# AUAV-X1_FMU_R1.net
KiCad netlist of a schematic drawn in Altium Designer
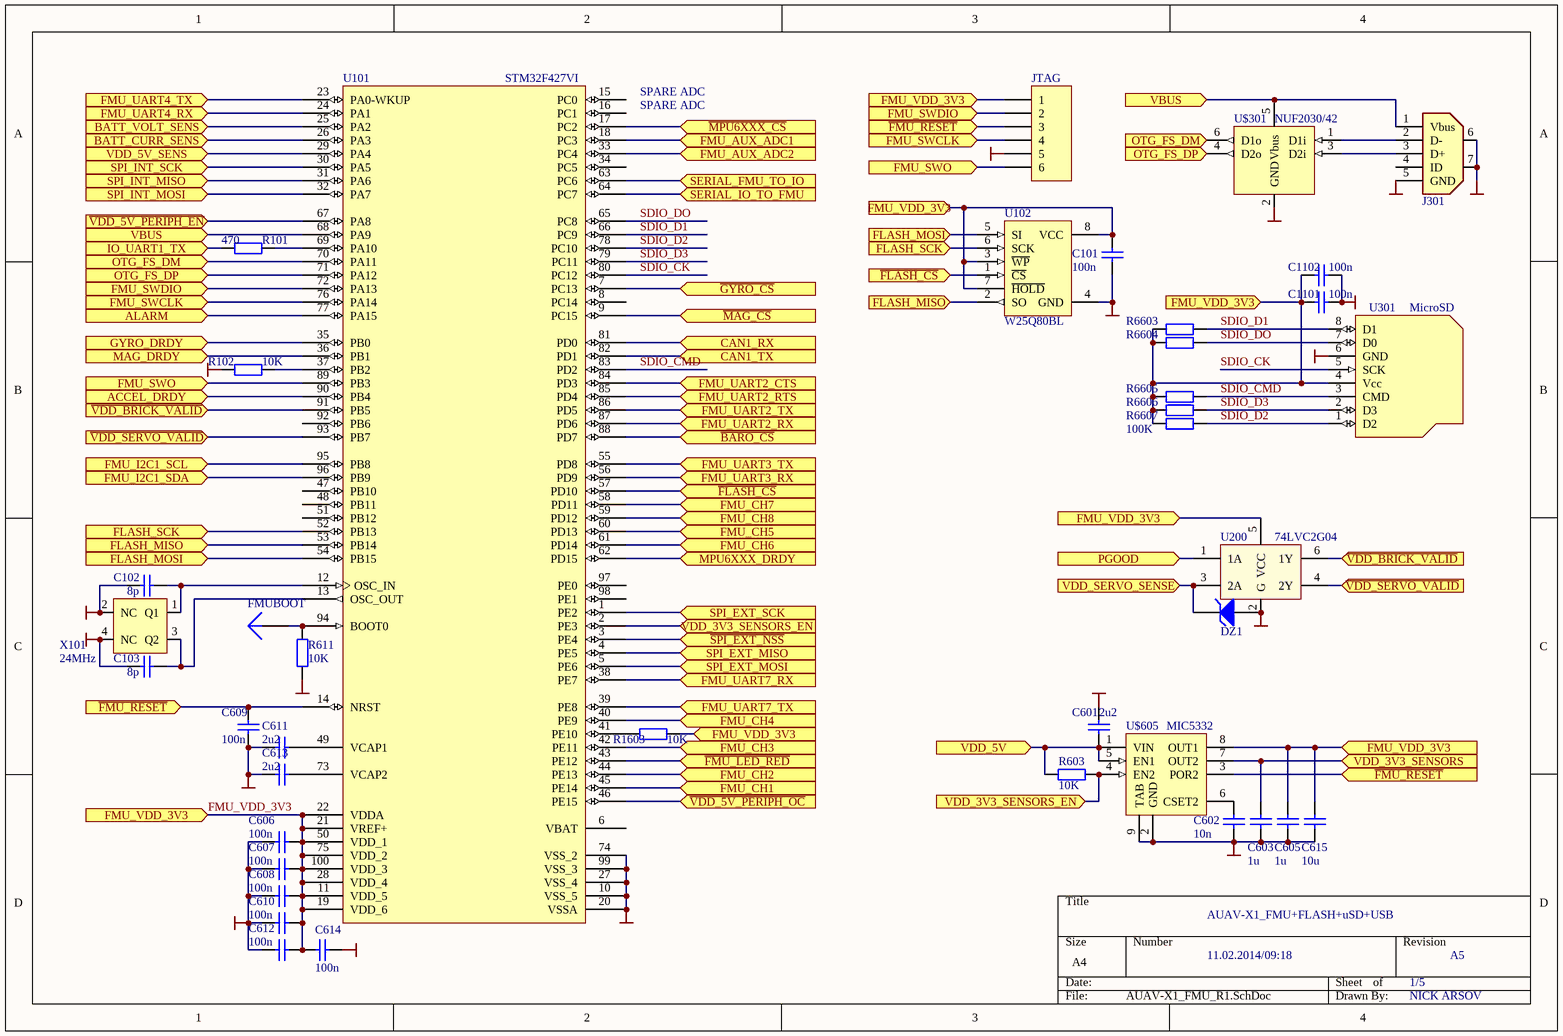
[diagram p0: AUAV-X1_FMU_R1.SchDoc]

(export (version "E")
  (design (tool "Eeschema 10.0.6"))
  (components
    (comp (ref "C101")
      (value "100n")
      (footprint "0402A")
      (description "Capacitor")
      (fields (field (name "PUBLISHER") "Altium Limited"))
      (libsource (lib "Miscellaneous Devices") (part "Cap"))
    )
    (comp (ref "C102")
      (value "8p")
      (footprint "0402A")
      (description "Capacitor")
      (fields (field (name "PUBLISHER") "Altium Limited"))
      (libsource (lib "Miscellaneous Devices") (part "Cap"))
    )
    (comp (ref "C103")
      (value "8p")
      (footprint "0402A")
      (description "Capacitor")
      (fields (field (name "PUBLISHER") "Altium Limited"))
      (libsource (lib "Miscellaneous Devices") (part "Cap"))
    )
    (comp (ref "C601")
      (value "2u2")
      (footprint "0402A")
      (description "Capacitor")
      (fields (field (name "PUBLISHER") "Altium Limited"))
      (libsource (lib "Miscellaneous Devices") (part "Cap"))
    )
    (comp (ref "C602")
      (value "10n")
      (footprint "0402A")
      (description "Capacitor")
      (fields (field (name "PUBLISHER") "Altium Limited"))
      (libsource (lib "Miscellaneous Devices") (part "Cap"))
    )
    (comp (ref "C603")
      (value "1u")
      (footprint "0402A")
      (description "Capacitor")
      (fields (field (name "PUBLISHER") "Altium Limited"))
      (libsource (lib "Miscellaneous Devices") (part "Cap"))
    )
    (comp (ref "C605")
      (value "1u")
      (footprint "0402A")
      (description "Capacitor")
      (fields (field (name "PUBLISHER") "Altium Limited"))
      (libsource (lib "Miscellaneous Devices") (part "Cap"))
    )
    (comp (ref "C606")
      (value "100n")
      (footprint "0402A")
      (description "Capacitor")
      (fields (field (name "PUBLISHER") "Altium Limited"))
      (libsource (lib "Miscellaneous Devices") (part "Cap"))
    )
    (comp (ref "C607")
      (value "100n")
      (footprint "0402A")
      (description "Capacitor")
      (fields (field (name "PUBLISHER") "Altium Limited"))
      (libsource (lib "Miscellaneous Devices") (part "Cap"))
    )
    (comp (ref "C608")
      (value "100n")
      (footprint "0402A")
      (description "Capacitor")
      (fields (field (name "PUBLISHER") "Altium Limited"))
      (libsource (lib "Miscellaneous Devices") (part "Cap"))
    )
    (comp (ref "C609")
      (value "100n")
      (footprint "0402A")
      (description "Capacitor")
      (fields (field (name "PUBLISHER") "Altium Limited"))
      (libsource (lib "Miscellaneous Devices") (part "Cap"))
    )
    (comp (ref "C610")
      (value "100n")
      (footprint "0402A")
      (description "Capacitor")
      (fields (field (name "PUBLISHER") "Altium Limited"))
      (libsource (lib "Miscellaneous Devices") (part "Cap"))
    )
    (comp (ref "C611")
      (value "2u2")
      (footprint "0402A")
      (description "Capacitor")
      (fields (field (name "PUBLISHER") "Altium Limited"))
      (libsource (lib "Miscellaneous Devices") (part "Cap"))
    )
    (comp (ref "C612")
      (value "100n")
      (footprint "0402A")
      (description "Capacitor")
      (fields (field (name "PUBLISHER") "Altium Limited"))
      (libsource (lib "Miscellaneous Devices") (part "Cap"))
    )
    (comp (ref "C613")
      (value "2u2")
      (footprint "0402A")
      (description "Capacitor")
      (fields (field (name "PUBLISHER") "Altium Limited"))
      (libsource (lib "Miscellaneous Devices") (part "Cap"))
    )
    (comp (ref "C614")
      (value "100n")
      (footprint "0402A")
      (description "Capacitor")
      (fields (field (name "PUBLISHER") "Altium Limited"))
      (libsource (lib "Miscellaneous Devices") (part "Cap"))
    )
    (comp (ref "C615")
      (value "10u")
      (footprint "0402A")
      (description "Capacitor")
      (fields (field (name "PUBLISHER") "Altium Limited"))
      (libsource (lib "Miscellaneous Devices") (part "Cap"))
    )
    (comp (ref "C1101")
      (value "100n")
      (footprint "0402A")
      (description "Capacitor")
      (fields (field (name "PUBLISHER") "Altium Limited"))
      (libsource (lib "Miscellaneous Devices") (part "Cap"))
    )
    (comp (ref "C1102")
      (value "100n")
      (footprint "0402A")
      (description "Capacitor")
      (fields (field (name "PUBLISHER") "Altium Limited"))
      (libsource (lib "Miscellaneous Devices") (part "Cap"))
    )
    (comp (ref "DZ1")
      (value "D Zener")
      (footprint "SOD-523")
      (description "Zener Diode")
      (fields (field (name "PUBLISHER") "Altium Limited"))
      (libsource (lib "Miscellaneous Devices") (part "D Zener"))
    )
    (comp (ref "FMUBOOT")
      (value "Plug")
      (footprint "PAD1")
      (fields (field (name "PUBLISHER") "Altium Limited"))
      (libsource (lib "Miscellaneous Connectors") (part "Plug"))
    )
    (comp (ref "J301")
      (value "miniUSB")
      (footprint "USBmicro_B")
      (libsource (lib "My_Altium") (part "MicroUSB"))
    )
    (comp (ref "JTAG")
      (value "Header 6")
      (footprint "JTAG_TC2030")
      (description "Header, 6-Pin")
      (fields (field (name "PUBLISHER") "Altium Limited"))
      (libsource (lib "Miscellaneous Connectors") (part "Header 6"))
    )
    (comp (ref "R101")
      (value "470")
      (footprint "0402A")
      (description "Resistor")
      (fields (field (name "PUBLISHER") "Altium Limited"))
      (libsource (lib "") (part "Res2_1"))
    )
    (comp (ref "R102")
      (value "10K")
      (footprint "0402A")
      (description "Resistor")
      (fields (field (name "PUBLISHER") "Altium Limited"))
      (libsource (lib "") (part "Res2_1"))
    )
    (comp (ref "R603")
      (value "10K")
      (footprint "0402A")
      (description "Resistor")
      (fields (field (name "PUBLISHER") "Altium Limited"))
      (libsource (lib "") (part "Res2_1"))
    )
    (comp (ref "R611")
      (value "10K")
      (footprint "0402A")
      (description "Resistor")
      (fields (field (name "PUBLISHER") "Altium Limited"))
      (libsource (lib "Miscellaneous Devices") (part "Res2"))
    )
    (comp (ref "R1603")
      (value "10K")
      (footprint "0402A")
      (description "Resistor")
      (fields (field (name "PUBLISHER") "Altium Limited"))
      (libsource (lib "") (part "Res2_1"))
    )
    (comp (ref "R6603")
      (value "100K")
      (footprint "0402A")
      (description "Resistor")
      (fields (field (name "PUBLISHER") "Altium Limited"))
      (libsource (lib "") (part "Res2_1"))
    )
    (comp (ref "R6604")
      (value "100K")
      (footprint "0402A")
      (description "Resistor")
      (fields (field (name "PUBLISHER") "Altium Limited"))
      (libsource (lib "") (part "Res2_1"))
    )
    (comp (ref "R6605")
      (value "100K")
      (footprint "0402A")
      (description "Resistor")
      (fields (field (name "PUBLISHER") "Altium Limited"))
      (libsource (lib "") (part "Res2_1"))
    )
    (comp (ref "R6606")
      (value "100K")
      (footprint "0402A")
      (description "Resistor")
      (fields (field (name "PUBLISHER") "Altium Limited"))
      (libsource (lib "") (part "Res2_1"))
    )
    (comp (ref "R6607")
      (value "100K")
      (footprint "0402A")
      (description "Resistor")
      (fields (field (name "PUBLISHER") "Altium Limited"))
      (libsource (lib "") (part "Res2_1"))
    )
    (comp (ref "U$301")
      (value "NUF2030/42")
      (footprint "NUF2030_SOT563")
      (libsource (lib "My_Altium") (part "NUF2030/42"))
    )
    (comp (ref "U$605")
      (value "MIC5332")
      (footprint "MIC5332")
      (libsource (lib "My_Altium") (part "MIC5332"))
    )
    (comp (ref "U101")
      (value "STM32F427VI")
      (footprint "LQFP100_L")
      (description "STM32 ARM-based 32-bit MCU with 64 Kbytes Flash, 100-pin LQFP, Industrial Temperature")
      (fields (field (name "PUBLISHER") "Altium Limited"))
      (libsource (lib "ST Microcontroller 32-Bit STM32") (part "STM32F103VBT6"))
    )
    (comp (ref "U102")
      (value "W25Q80BL")
      (footprint "W25Q80BL_WSON5X6")
      (libsource (lib "My_Altium") (part "AT45DB161D-MU"))
    )
    (comp (ref "U200")
      (value "74LVC2G04")
      (footprint "SOT363_L")
      (libsource (lib "My_Altium") (part "74LVC2G04"))
    )
    (comp (ref "U301")
      (value "MicroSD")
      (footprint "MicroSD_China_01")
      (libsource (lib "My_Altium") (part "MicroSD"))
    )
    (comp (ref "X101")
      (value "24MHz")
      (footprint "Crystal_2.5x2")
      (libsource (lib "My_Altium") (part "Crystal_4pin"))
    )
  )
  (nets
    (net (code "1") (name "/ACCEL_DRDY") (class "Default")
      (node (ref "U101") (pin "90") (pinfunction "PB4_90") (pintype "bidirectional"))
    )
    (net (code "2") (name "/ALARM") (class "Default")
      (node (ref "U101") (pin "77") (pinfunction "PA15_77") (pintype "bidirectional"))
    )
    (net (code "3") (name "/BATT_CURR_SENS") (class "Default")
      (node (ref "U101") (pin "26") (pinfunction "PA3_26") (pintype "bidirectional"))
    )
    (net (code "4") (name "/BATT_VOLT_SENS") (class "Default")
      (node (ref "U101") (pin "25") (pinfunction "PA2_25") (pintype "bidirectional"))
    )
    (net (code "5") (name "/CAN1_RX") (class "Default")
      (node (ref "U101") (pin "81") (pinfunction "PD0_81") (pintype "bidirectional"))
    )
    (net (code "6") (name "/CAN1_TX") (class "Default")
      (node (ref "U101") (pin "82") (pinfunction "PD1_82") (pintype "bidirectional"))
    )
    (net (code "7") (name "/FLASH_MISO") (class "Default")
      (node (ref "U101") (pin "53") (pinfunction "PB14_53") (pintype "bidirectional"))
      (node (ref "U102") (pin "2") (pinfunction "SO_2") (pintype "output"))
    )
    (net (code "8") (name "/FLASH_MOSI") (class "Default")
      (node (ref "U101") (pin "54") (pinfunction "PB15_54") (pintype "bidirectional"))
      (node (ref "U102") (pin "5") (pinfunction "SI_5") (pintype "input"))
    )
    (net (code "9") (name "/FLASH_SCK") (class "Default")
      (node (ref "U101") (pin "52") (pinfunction "PB13_52") (pintype "bidirectional"))
      (node (ref "U102") (pin "6") (pinfunction "SCK_6") (pintype "input"))
    )
    (net (code "10") (name "/FMU_AUX_ADC1") (class "Default")
      (node (ref "U101") (pin "18") (pinfunction "PC3_18") (pintype "bidirectional"))
    )
    (net (code "11") (name "/FMU_AUX_ADC2") (class "Default")
      (node (ref "U101") (pin "33") (pinfunction "PC4_33") (pintype "bidirectional"))
    )
    (net (code "12") (name "/FMU_CH1") (class "Default")
      (node (ref "U101") (pin "45") (pinfunction "PE14_45") (pintype "bidirectional"))
    )
    (net (code "13") (name "/FMU_CH2") (class "Default")
      (node (ref "U101") (pin "44") (pinfunction "PE13_44") (pintype "bidirectional"))
    )
    (net (code "14") (name "/FMU_CH3") (class "Default")
      (node (ref "U101") (pin "42") (pinfunction "PE11_42") (pintype "bidirectional"))
    )
    (net (code "15") (name "/FMU_CH4") (class "Default")
      (node (ref "U101") (pin "40") (pinfunction "PE9_40") (pintype "bidirectional"))
    )
    (net (code "16") (name "/FMU_CH5") (class "Default")
      (node (ref "U101") (pin "60") (pinfunction "PD13_60") (pintype "bidirectional"))
    )
    (net (code "17") (name "/FMU_CH6") (class "Default")
      (node (ref "U101") (pin "61") (pinfunction "PD14_61") (pintype "bidirectional"))
    )
    (net (code "18") (name "/FMU_CH7") (class "Default")
      (node (ref "U101") (pin "58") (pinfunction "PD11_58") (pintype "bidirectional"))
    )
    (net (code "19") (name "/FMU_CH8") (class "Default")
      (node (ref "U101") (pin "59") (pinfunction "PD12_59") (pintype "bidirectional"))
    )
    (net (code "20") (name "/FMU_I2C1_SCL") (class "Default")
      (node (ref "U101") (pin "95") (pinfunction "PB8_95") (pintype "bidirectional"))
    )
    (net (code "21") (name "/FMU_I2C1_SDA") (class "Default")
      (node (ref "U101") (pin "96") (pinfunction "PB9_96") (pintype "bidirectional"))
    )
    (net (code "22") (name "/FMU_SWCLK") (class "Default")
      (node (ref "JTAG") (pin "4") (pinfunction "4_4") (pintype "passive"))
      (node (ref "U101") (pin "76") (pinfunction "PA14_76") (pintype "bidirectional"))
    )
    (net (code "23") (name "/FMU_SWDIO") (class "Default")
      (node (ref "JTAG") (pin "2") (pinfunction "2_2") (pintype "passive"))
      (node (ref "U101") (pin "72") (pinfunction "PA13_72") (pintype "bidirectional"))
    )
    (net (code "24") (name "/FMU_SWO") (class "Default")
      (node (ref "JTAG") (pin "6") (pinfunction "6_6") (pintype "passive"))
      (node (ref "U101") (pin "89") (pinfunction "PB3_89") (pintype "bidirectional"))
    )
    (net (code "25") (name "/FMU_UART2_CTS") (class "Default")
      (node (ref "U101") (pin "84") (pinfunction "PD3_84") (pintype "bidirectional"))
    )
    (net (code "26") (name "/FMU_UART2_RTS") (class "Default")
      (node (ref "U101") (pin "85") (pinfunction "PD4_85") (pintype "bidirectional"))
    )
    (net (code "27") (name "/FMU_UART2_RX") (class "Default")
      (node (ref "U101") (pin "87") (pinfunction "PD6_87") (pintype "bidirectional"))
    )
    (net (code "28") (name "/FMU_UART2_TX") (class "Default")
      (node (ref "U101") (pin "86") (pinfunction "PD5_86") (pintype "bidirectional"))
    )
    (net (code "29") (name "/FMU_UART3_RX") (class "Default")
      (node (ref "U101") (pin "56") (pinfunction "PD9_56") (pintype "bidirectional"))
    )
    (net (code "30") (name "/FMU_UART3_TX") (class "Default")
      (node (ref "U101") (pin "55") (pinfunction "PD8_55") (pintype "bidirectional"))
    )
    (net (code "31") (name "/FMU_UART4_RX") (class "Default")
      (node (ref "U101") (pin "24") (pinfunction "PA1_24") (pintype "bidirectional"))
    )
    (net (code "32") (name "/FMU_UART4_TX") (class "Default")
      (node (ref "U101") (pin "23") (pinfunction "PA0-WKUP_23") (pintype "bidirectional"))
    )
    (net (code "33") (name "/FMU_UART7_RX") (class "Default")
      (node (ref "U101") (pin "38") (pinfunction "PE7_38") (pintype "bidirectional"))
    )
    (net (code "34") (name "/FMU_UART7_TX") (class "Default")
      (node (ref "U101") (pin "39") (pinfunction "PE8_39") (pintype "bidirectional"))
    )
    (net (code "35") (name "/FMU_VDD_3V3") (class "Default")
      (node (ref "C101") (pin "2") (pinfunction "2_2") (pintype "passive"))
      (node (ref "C1101") (pin "2") (pinfunction "2_2") (pintype "passive"))
      (node (ref "C1102") (pin "2") (pinfunction "2_2") (pintype "passive"))
      (node (ref "C605") (pin "2") (pinfunction "2_2") (pintype "passive"))
      (node (ref "C606") (pin "2") (pinfunction "2_2") (pintype "passive"))
      (node (ref "C607") (pin "2") (pinfunction "2_2") (pintype "passive"))
      (node (ref "C608") (pin "2") (pinfunction "2_2") (pintype "passive"))
      (node (ref "C610") (pin "2") (pinfunction "2_2") (pintype "passive"))
      (node (ref "C612") (pin "2") (pinfunction "2_2") (pintype "passive"))
      (node (ref "C614") (pin "2") (pinfunction "2_2") (pintype "passive"))
      (node (ref "C615") (pin "2") (pinfunction "2_2") (pintype "passive"))
      (node (ref "JTAG") (pin "1") (pinfunction "1_1") (pintype "passive"))
      (node (ref "R1603") (pin "2") (pinfunction "2_2") (pintype "passive"))
      (node (ref "R6603") (pin "1") (pinfunction "1_1") (pintype "passive"))
      (node (ref "R6604") (pin "1") (pinfunction "1_1") (pintype "passive"))
      (node (ref "R6605") (pin "1") (pinfunction "1_1") (pintype "passive"))
      (node (ref "R6606") (pin "1") (pinfunction "1_1") (pintype "passive"))
      (node (ref "R6607") (pin "1") (pinfunction "1_1") (pintype "passive"))
      (node (ref "U$605") (pin "8") (pinfunction "OUT1_8") (pintype "passive"))
      (node (ref "U101") (pin "100") (pinfunction "VDD_3_100") (pintype "power_in"))
      (node (ref "U101") (pin "11") (pinfunction "VDD_5_11") (pintype "power_in"))
      (node (ref "U101") (pin "19") (pinfunction "VDD_6_19") (pintype "power_in"))
      (node (ref "U101") (pin "21") (pinfunction "VREF+_21") (pintype "power_in"))
      (node (ref "U101") (pin "22") (pinfunction "VDDA_22") (pintype "power_in"))
      (node (ref "U101") (pin "28") (pinfunction "VDD_4_28") (pintype "power_in"))
      (node (ref "U101") (pin "50") (pinfunction "VDD_1_50") (pintype "power_in"))
      (node (ref "U101") (pin "75") (pinfunction "VDD_2_75") (pintype "power_in"))
      (node (ref "U102") (pin "3") (pinfunction "~{WP}_3") (pintype "input"))
      (node (ref "U102") (pin "7") (pinfunction "~{HOLD}_7") (pintype "passive"))
      (node (ref "U102") (pin "8") (pinfunction "VCC_8") (pintype "power_in"))
      (node (ref "U200") (pin "5") (pinfunction "VCC_5") (pintype "power_in"))
      (node (ref "U301") (pin "4") (pinfunction "Vcc_4") (pintype "power_in"))
    )
    (net (code "36") (name "/GYRO_DRDY") (class "Default")
      (node (ref "U101") (pin "35") (pinfunction "PB0_35") (pintype "bidirectional"))
    )
    (net (code "37") (name "/IO_UART1_TX") (class "Default")
      (node (ref "R101") (pin "1") (pinfunction "1_1") (pintype "passive"))
    )
    (net (code "38") (name "/MAG_DRDY") (class "Default")
      (node (ref "U101") (pin "36") (pinfunction "PB1_36") (pintype "bidirectional"))
    )
    (net (code "39") (name "/MPU6XXX_DRDY") (class "Default")
      (node (ref "U101") (pin "62") (pinfunction "PD15_62") (pintype "bidirectional"))
    )
    (net (code "40") (name "/OTG_FS_DM") (class "Default")
      (node (ref "U$301") (pin "6") (pinfunction "D1o_6") (pintype "output"))
      (node (ref "U101") (pin "70") (pinfunction "PA11_70") (pintype "bidirectional"))
    )
    (net (code "41") (name "/OTG_FS_DP") (class "Default")
      (node (ref "U$301") (pin "4") (pinfunction "D2o_4") (pintype "output"))
      (node (ref "U101") (pin "71") (pinfunction "PA12_71") (pintype "bidirectional"))
    )
    (net (code "42") (name "/PGOOD") (class "Default")
      (node (ref "U200") (pin "1") (pinfunction "1A_1") (pintype "passive"))
    )
    (net (code "43") (name "/SDIO_CK") (class "Default")
      (node (ref "U101") (pin "80") (pinfunction "PC12_80") (pintype "bidirectional"))
      (node (ref "U301") (pin "5") (pinfunction "SCK_5") (pintype "input"))
    )
    (net (code "44") (name "/SDIO_CMD") (class "Default")
      (node (ref "R6605") (pin "2") (pinfunction "2_2") (pintype "passive"))
      (node (ref "U101") (pin "83") (pinfunction "PD2_83") (pintype "bidirectional"))
      (node (ref "U301") (pin "3") (pinfunction "CMD_3") (pintype "passive"))
    )
    (net (code "45") (name "/SDIO_D1") (class "Default")
      (node (ref "R6603") (pin "2") (pinfunction "2_2") (pintype "passive"))
      (node (ref "U101") (pin "66") (pinfunction "PC9_66") (pintype "bidirectional"))
      (node (ref "U301") (pin "8") (pinfunction "D1_8") (pintype "bidirectional"))
    )
    (net (code "46") (name "/SDIO_D2") (class "Default")
      (node (ref "R6607") (pin "2") (pinfunction "2_2") (pintype "passive"))
      (node (ref "U101") (pin "78") (pinfunction "PC10_78") (pintype "bidirectional"))
      (node (ref "U301") (pin "1") (pinfunction "D2_1") (pintype "bidirectional"))
    )
    (net (code "47") (name "/SDIO_D3") (class "Default")
      (node (ref "R6606") (pin "2") (pinfunction "2_2") (pintype "passive"))
      (node (ref "U101") (pin "79") (pinfunction "PC11_79") (pintype "bidirectional"))
      (node (ref "U301") (pin "2") (pinfunction "D3_2") (pintype "bidirectional"))
    )
    (net (code "48") (name "/SDIO_DO") (class "Default")
      (node (ref "R6604") (pin "2") (pinfunction "2_2") (pintype "passive"))
      (node (ref "U101") (pin "65") (pinfunction "PC8_65") (pintype "bidirectional"))
      (node (ref "U301") (pin "7") (pinfunction "D0_7") (pintype "bidirectional"))
    )
    (net (code "49") (name "/SERIAL_FMU_TO_IO") (class "Default")
      (node (ref "U101") (pin "63") (pinfunction "PC6_63") (pintype "bidirectional"))
    )
    (net (code "50") (name "/SERIAL_IO_TO_FMU") (class "Default")
      (node (ref "U101") (pin "64") (pinfunction "PC7_64") (pintype "bidirectional"))
    )
    (net (code "51") (name "/SPI_EXT_MISO") (class "Default")
      (node (ref "U101") (pin "4") (pinfunction "PE5_4") (pintype "bidirectional"))
    )
    (net (code "52") (name "/SPI_EXT_MOSI") (class "Default")
      (node (ref "U101") (pin "5") (pinfunction "PE6_5") (pintype "bidirectional"))
    )
    (net (code "53") (name "/SPI_EXT_SCK") (class "Default")
      (node (ref "U101") (pin "1") (pinfunction "PE2_1") (pintype "bidirectional"))
    )
    (net (code "54") (name "/SPI_INT_MISO") (class "Default")
      (node (ref "U101") (pin "31") (pinfunction "PA6_31") (pintype "bidirectional"))
    )
    (net (code "55") (name "/SPI_INT_MOSI") (class "Default")
      (node (ref "U101") (pin "32") (pinfunction "PA7_32") (pintype "bidirectional"))
    )
    (net (code "56") (name "/SPI_INT_SCK") (class "Default")
      (node (ref "U101") (pin "30") (pinfunction "PA5_30") (pintype "bidirectional"))
    )
    (net (code "57") (name "/VBUS") (class "Default")
      (node (ref "J301") (pin "1") (pinfunction "Vbus_1") (pintype "power_in"))
      (node (ref "U$301") (pin "5") (pinfunction "Vbus_5") (pintype "power_in"))
      (node (ref "U101") (pin "68") (pinfunction "PA9_68") (pintype "bidirectional"))
    )
    (net (code "58") (name "/VDD_3V3_SENSORS") (class "Default")
      (node (ref "C603") (pin "2") (pinfunction "2_2") (pintype "passive"))
      (node (ref "U$605") (pin "7") (pinfunction "OUT2_7") (pintype "passive"))
    )
    (net (code "59") (name "/VDD_3V3_SENSORS_EN") (class "Default")
      (node (ref "R603") (pin "2") (pinfunction "2_2") (pintype "passive"))
      (node (ref "U$605") (pin "4") (pinfunction "EN2_4") (pintype "input"))
      (node (ref "U101") (pin "2") (pinfunction "PE3_2") (pintype "bidirectional"))
    )
    (net (code "60") (name "/VDD_5V") (class "Default")
      (node (ref "C601") (pin "1") (pinfunction "1_1") (pintype "passive"))
      (node (ref "R603") (pin "1") (pinfunction "1_1") (pintype "passive"))
      (node (ref "U$605") (pin "1") (pinfunction "VIN_1") (pintype "power_in"))
      (node (ref "U$605") (pin "5") (pinfunction "EN1_5") (pintype "input"))
    )
    (net (code "61") (name "/VDD_5V_SENS") (class "Default")
      (node (ref "U101") (pin "29") (pinfunction "PA4_29") (pintype "bidirectional"))
    )
    (net (code "62") (name "/VDD_SERVO_SENSE") (class "Default")
      (node (ref "DZ1") (pin "1") (pinfunction "A_1") (pintype "passive"))
      (node (ref "U200") (pin "3") (pinfunction "2A_3") (pintype "passive"))
    )
    (net (code "63") (name "/~{BARO_CS}") (class "Default")
      (node (ref "U101") (pin "88") (pinfunction "PD7_88") (pintype "bidirectional"))
    )
    (net (code "64") (name "/~{FLASH_CS}") (class "Default")
      (node (ref "U101") (pin "57") (pinfunction "PD10_57") (pintype "bidirectional"))
      (node (ref "U102") (pin "1") (pinfunction "~{CS}_1") (pintype "input"))
    )
    (net (code "65") (name "/~{FMU_LED_RED}") (class "Default")
      (node (ref "U101") (pin "43") (pinfunction "PE12_43") (pintype "bidirectional"))
    )
    (net (code "66") (name "/~{FMU_RESET}") (class "Default")
      (node (ref "C609") (pin "2") (pinfunction "2_2") (pintype "passive"))
      (node (ref "JTAG") (pin "3") (pinfunction "3_3") (pintype "passive"))
      (node (ref "U$605") (pin "3") (pinfunction "POR2_3") (pintype "passive"))
      (node (ref "U101") (pin "14") (pinfunction "NRST_14") (pintype "bidirectional"))
    )
    (net (code "67") (name "/~{GYRO_CS}") (class "Default")
      (node (ref "U101") (pin "7") (pinfunction "PC13_7") (pintype "bidirectional"))
    )
    (net (code "68") (name "/~{MAG_CS}") (class "Default")
      (node (ref "U101") (pin "9") (pinfunction "PC15_9") (pintype "bidirectional"))
    )
    (net (code "69") (name "/~{MPU6XXX_CS}") (class "Default")
      (node (ref "U101") (pin "17") (pinfunction "PC2_17") (pintype "bidirectional"))
    )
    (net (code "70") (name "/~{SPI_EXT_NSS}") (class "Default")
      (node (ref "U101") (pin "3") (pinfunction "PE4_3") (pintype "bidirectional"))
    )
    (net (code "71") (name "/~{VDD_5V_PERIPH_EN}") (class "Default")
      (node (ref "U101") (pin "67") (pinfunction "PA8_67") (pintype "bidirectional"))
    )
    (net (code "72") (name "/~{VDD_5V_PERIPH_OC}") (class "Default")
      (node (ref "U101") (pin "46") (pinfunction "PE15_46") (pintype "bidirectional"))
    )
    (net (code "73") (name "/~{VDD_BRICK_VALID}") (class "Default")
      (node (ref "U101") (pin "91") (pinfunction "PB5_91") (pintype "bidirectional"))
      (node (ref "U200") (pin "6") (pinfunction "1Y_6") (pintype "passive"))
    )
    (net (code "74") (name "/~{VDD_SERVO_VALID}") (class "Default")
      (node (ref "U101") (pin "93") (pinfunction "PB7_93") (pintype "bidirectional"))
      (node (ref "U200") (pin "4") (pinfunction "2Y_4") (pintype "passive"))
    )
    (net (code "75") (name "GND") (class "Default")
      (node (ref "C101") (pin "1") (pinfunction "1_1") (pintype "passive"))
      (node (ref "C102") (pin "1") (pinfunction "1_1") (pintype "passive"))
      (node (ref "C103") (pin "1") (pinfunction "1_1") (pintype "passive"))
      (node (ref "C1101") (pin "1") (pinfunction "1_1") (pintype "passive"))
      (node (ref "C1102") (pin "1") (pinfunction "1_1") (pintype "passive"))
      (node (ref "C601") (pin "2") (pinfunction "2_2") (pintype "passive"))
      (node (ref "C602") (pin "1") (pinfunction "1_1") (pintype "passive"))
      (node (ref "C603") (pin "1") (pinfunction "1_1") (pintype "passive"))
      (node (ref "C605") (pin "1") (pinfunction "1_1") (pintype "passive"))
      (node (ref "C606") (pin "1") (pinfunction "1_1") (pintype "passive"))
      (node (ref "C607") (pin "1") (pinfunction "1_1") (pintype "passive"))
      (node (ref "C608") (pin "1") (pinfunction "1_1") (pintype "passive"))
      (node (ref "C609") (pin "1") (pinfunction "1_1") (pintype "passive"))
      (node (ref "C610") (pin "1") (pinfunction "1_1") (pintype "passive"))
      (node (ref "C611") (pin "1") (pinfunction "1_1") (pintype "passive"))
      (node (ref "C612") (pin "1") (pinfunction "1_1") (pintype "passive"))
      (node (ref "C613") (pin "1") (pinfunction "1_1") (pintype "passive"))
      (node (ref "C614") (pin "1") (pinfunction "1_1") (pintype "passive"))
      (node (ref "C615") (pin "1") (pinfunction "1_1") (pintype "passive"))
      (node (ref "DZ1") (pin "2") (pinfunction "K_2") (pintype "passive"))
      (node (ref "J301") (pin "5") (pinfunction "GND_5") (pintype "power_in"))
      (node (ref "J301") (pin "6") (pinfunction "GND_6") (pintype "passive"))
      (node (ref "J301") (pin "7") (pinfunction "GND_7") (pintype "passive"))
      (node (ref "JTAG") (pin "5") (pinfunction "5_5") (pintype "passive"))
      (node (ref "R102") (pin "1") (pinfunction "1_1") (pintype "passive"))
      (node (ref "R611") (pin "1") (pinfunction "1_1") (pintype "passive"))
      (node (ref "U$301") (pin "2") (pinfunction "GND_2") (pintype "power_in"))
      (node (ref "U$605") (pin "2") (pinfunction "GND_2") (pintype "power_in"))
      (node (ref "U$605") (pin "9") (pinfunction "TAB_9") (pintype "power_in"))
      (node (ref "U101") (pin "10") (pinfunction "VSS_5_10") (pintype "power_in"))
      (node (ref "U101") (pin "20") (pinfunction "VSSA_20") (pintype "power_in"))
      (node (ref "U101") (pin "27") (pinfunction "VSS_4_27") (pintype "power_in"))
      (node (ref "U101") (pin "74") (pinfunction "VSS_2_74") (pintype "power_in"))
      (node (ref "U101") (pin "99") (pinfunction "VSS_3_99") (pintype "power_in"))
      (node (ref "U102") (pin "4") (pinfunction "GND_4") (pintype "power_in"))
      (node (ref "U200") (pin "2") (pinfunction "G_2") (pintype "power_in"))
      (node (ref "U301") (pin "6") (pinfunction "GND_6") (pintype "power_in"))
      (node (ref "X101") (pin "2") (pinfunction "NC_2") (pintype "passive"))
      (node (ref "X101") (pin "4") (pinfunction "NC_4") (pintype "passive"))
    )
    (net (code "76") (name "Net-(J301-D+)") (class "Default")
      (node (ref "J301") (pin "3") (pinfunction "D+_3") (pintype "passive"))
      (node (ref "U$301") (pin "3") (pinfunction "D2i_3") (pintype "input"))
    )
    (net (code "77") (name "Net-(J301-D-)") (class "Default")
      (node (ref "J301") (pin "2") (pinfunction "D-_2") (pintype "passive"))
      (node (ref "U$301") (pin "1") (pinfunction "D1i_1") (pintype "input"))
    )
    (net (code "78") (name "Net-(U$605-CSET2)") (class "Default")
      (node (ref "C602") (pin "2") (pinfunction "2_2") (pintype "passive"))
      (node (ref "U$605") (pin "6") (pinfunction "CSET2_6") (pintype "passive"))
    )
    (net (code "79") (name "Net-(U101-BOOT0)") (class "Default")
      (node (ref "FMUBOOT") (pin "1") (pinfunction "1_1") (pintype "passive"))
      (node (ref "R611") (pin "2") (pinfunction "2_2") (pintype "passive"))
      (node (ref "U101") (pin "94") (pinfunction "BOOT0_94") (pintype "input"))
    )
    (net (code "80") (name "Net-(U101-OSC_IN)") (class "Default")
      (node (ref "C102") (pin "2") (pinfunction "2_2") (pintype "passive"))
      (node (ref "U101") (pin "12") (pinfunction "OSC_IN_12") (pintype "input"))
      (node (ref "X101") (pin "1") (pinfunction "Q1_1") (pintype "passive"))
    )
    (net (code "81") (name "Net-(U101-OSC_OUT)") (class "Default")
      (node (ref "C103") (pin "2") (pinfunction "2_2") (pintype "passive"))
      (node (ref "U101") (pin "13") (pinfunction "OSC_OUT_13") (pintype "output"))
      (node (ref "X101") (pin "3") (pinfunction "Q2_3") (pintype "passive"))
    )
    (net (code "82") (name "Net-(U101-PA10)") (class "Default")
      (node (ref "R101") (pin "2") (pinfunction "2_2") (pintype "passive"))
      (node (ref "U101") (pin "69") (pinfunction "PA10_69") (pintype "bidirectional"))
    )
    (net (code "83") (name "Net-(U101-PB2)") (class "Default")
      (node (ref "R102") (pin "2") (pinfunction "2_2") (pintype "passive"))
      (node (ref "U101") (pin "37") (pinfunction "PB2_37") (pintype "bidirectional"))
    )
    (net (code "84") (name "Net-(U101-PE10)") (class "Default")
      (node (ref "R1603") (pin "1") (pinfunction "1_1") (pintype "passive"))
      (node (ref "U101") (pin "41") (pinfunction "PE10_41") (pintype "bidirectional"))
    )
    (net (code "85") (name "Net-(U101-VCAP1)") (class "Default")
      (node (ref "C611") (pin "2") (pinfunction "2_2") (pintype "passive"))
      (node (ref "U101") (pin "49") (pinfunction "VCAP1_49") (pintype "passive"))
    )
    (net (code "86") (name "Net-(U101-VCAP2)") (class "Default")
      (node (ref "C613") (pin "2") (pinfunction "2_2") (pintype "passive"))
      (node (ref "U101") (pin "73") (pinfunction "VCAP2_73") (pintype "passive"))
    )
    (net (code "87") (name "unconnected-(J301-ID-Pad4)") (class "Default")
      (node (ref "J301") (pin "4") (pinfunction "ID_4") (pintype "passive"))
    )
    (net (code "88") (name "unconnected-(U101-PB6-Pad92)") (class "Default")
      (node (ref "U101") (pin "92") (pinfunction "PB6_92") (pintype "bidirectional"))
    )
    (net (code "89") (name "unconnected-(U101-PB10-Pad47)") (class "Default")
      (node (ref "U101") (pin "47") (pinfunction "PB10_47") (pintype "bidirectional"))
    )
    (net (code "90") (name "unconnected-(U101-PB11-Pad48)") (class "Default")
      (node (ref "U101") (pin "48") (pinfunction "PB11_48") (pintype "bidirectional"))
    )
    (net (code "91") (name "unconnected-(U101-PB12-Pad51)") (class "Default")
      (node (ref "U101") (pin "51") (pinfunction "PB12_51") (pintype "bidirectional"))
    )
    (net (code "92") (name "unconnected-(U101-PC0-Pad15)") (class "Default")
      (node (ref "U101") (pin "15") (pinfunction "PC0_15") (pintype "bidirectional"))
    )
    (net (code "93") (name "unconnected-(U101-PC1-Pad16)") (class "Default")
      (node (ref "U101") (pin "16") (pinfunction "PC1_16") (pintype "bidirectional"))
    )
    (net (code "94") (name "unconnected-(U101-PC5-Pad34)") (class "Default")
      (node (ref "U101") (pin "34") (pinfunction "PC5_34") (pintype "bidirectional"))
    )
    (net (code "95") (name "unconnected-(U101-PC14-Pad8)") (class "Default")
      (node (ref "U101") (pin "8") (pinfunction "PC14_8") (pintype "bidirectional"))
    )
    (net (code "96") (name "unconnected-(U101-PE0-Pad97)") (class "Default")
      (node (ref "U101") (pin "97") (pinfunction "PE0_97") (pintype "bidirectional"))
    )
    (net (code "97") (name "unconnected-(U101-PE1-Pad98)") (class "Default")
      (node (ref "U101") (pin "98") (pinfunction "PE1_98") (pintype "bidirectional"))
    )
    (net (code "98") (name "unconnected-(U101-VBAT-Pad6)") (class "Default")
      (node (ref "U101") (pin "6") (pinfunction "VBAT_6") (pintype "power_in"))
    )
  )
)
